# MotorX.net
KiCad netlist of a schematic drawn in Altium Designer
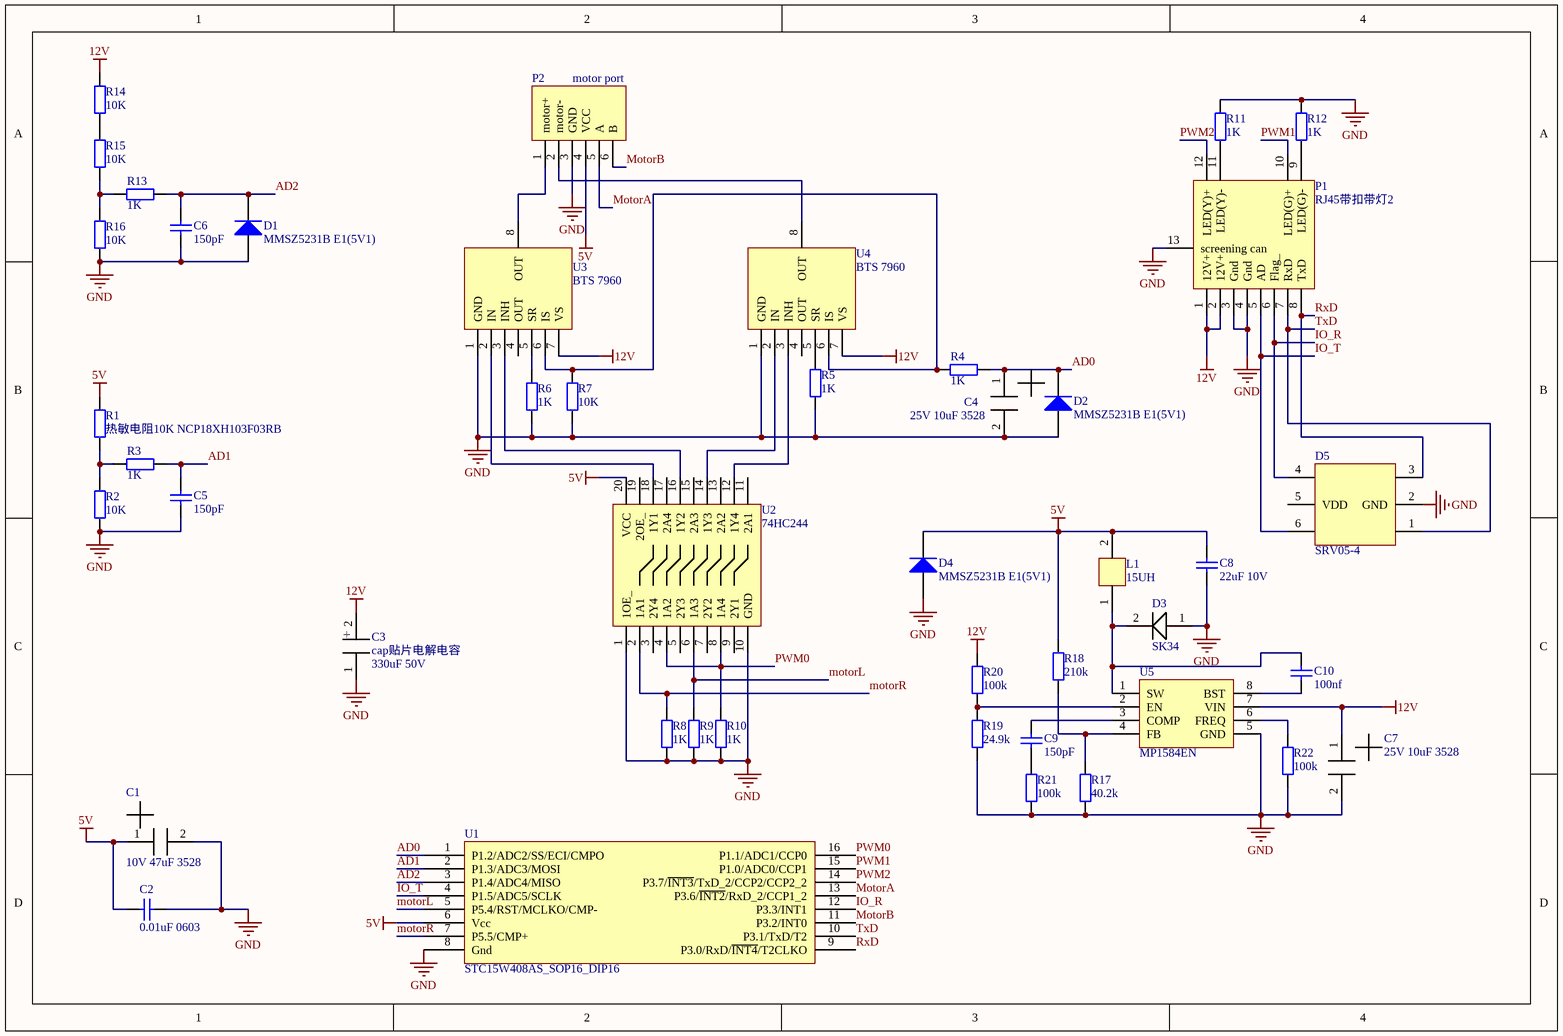
[diagram p0: MotorX.SchDoc]

(export (version "E")
  (design (tool "Eeschema 10.0.6"))
  (components
    (comp (ref "C1")
      (value "10V 47uF 3528")
      (footprint "贴片电容3528_2")
      (libsource (lib "贴片电容3528") (part "电容"))
    )
    (comp (ref "C2")
      (value "0.01uF 0603")
      (footprint "0603")
      (description "Capacitor")
      (fields (field (name "PUBLISHER") "Altium Limited"))
      (libsource (lib "Miscellaneous Devices") (part "Cap"))
    )
    (comp (ref "C3")
      (value "cap贴片电解电容")
      (footprint "贴片电解电容（10*10.2mm）")
      (fields (field (name "ALTIUM_UNNAMED_1") "330uF 50V"))
      (libsource (lib "贴片电容（10x10.2mm）") (part "cap贴片电容"))
    )
    (comp (ref "C4")
      (value "25V 10uF 3528")
      (footprint "贴片电容3528_2")
      (libsource (lib "贴片电容3528") (part "电容"))
    )
    (comp (ref "C5")
      (value "150pF")
      (footprint "0603")
      (description "Capacitor")
      (fields (field (name "Comment") "Cap") (field (name "PUBLISHER") "Altium Limited"))
      (libsource (lib "Miscellaneous Devices") (part "Cap"))
    )
    (comp (ref "C6")
      (value "150pF")
      (footprint "0603")
      (description "Capacitor")
      (fields (field (name "Comment") "Cap") (field (name "PUBLISHER") "Altium Limited"))
      (libsource (lib "Miscellaneous Devices") (part "Cap"))
    )
    (comp (ref "C7")
      (value "25V 10uF 3528")
      (footprint "贴片电容3528_2")
      (libsource (lib "贴片电容3528") (part "电容"))
    )
    (comp (ref "C8")
      (value "22uF 10V")
      (footprint "0805")
      (description "Capacitor")
      (fields (field (name "Comment") "Cap") (field (name "PUBLISHER") "Altium Limited"))
      (libsource (lib "Miscellaneous Devices") (part "Cap"))
    )
    (comp (ref "C9")
      (value "150pF")
      (footprint "0603")
      (description "Capacitor")
      (fields (field (name "Comment") "Cap") (field (name "PUBLISHER") "Altium Limited"))
      (libsource (lib "Miscellaneous Devices") (part "Cap"))
    )
    (comp (ref "C10")
      (value "100nf")
      (footprint "0603")
      (description "Capacitor")
      (fields (field (name "Comment") "Cap") (field (name "PUBLISHER") "Altium Limited"))
      (libsource (lib "Miscellaneous Devices") (part "Cap"))
    )
    (comp (ref "D1")
      (value "MMSZ5231B E1(5V1)")
      (footprint "SOD-123_5")
      (description "High Conductance Fast Diode")
      (fields (field (name "PUBLISHER") "Altium Limited"))
      (libsource (lib "Miscellaneous Devices") (part "Diode 1N4148"))
    )
    (comp (ref "D2")
      (value "MMSZ5231B E1(5V1)")
      (footprint "SOD-123_5")
      (description "High Conductance Fast Diode")
      (fields (field (name "PUBLISHER") "Altium Limited"))
      (libsource (lib "Miscellaneous Devices") (part "Diode 1N4148"))
    )
    (comp (ref "D3") (value "SK34") (footprint "SK34") (libsource (lib "SK34二极管") (part "SK34")))
    (comp (ref "D4")
      (value "MMSZ5231B E1(5V1)")
      (footprint "SOD-123_5")
      (description "High Conductance Fast Diode")
      (fields (field (name "PUBLISHER") "Altium Limited"))
      (libsource (lib "Miscellaneous Devices") (part "Diode 1N4148"))
    )
    (comp (ref "D5")
      (value "SRV05-4")
      (footprint "sot-23-6(SRV05-4)")
      (libsource (lib "SRV05-4") (part "SRV05-4"))
    )
    (comp (ref "L1") (value "15UH") (footprint "0630功率电感") (libsource (lib "0630功率电感") (part "0630功率电感")))
    (comp (ref "P1")
      (value "RJ45带扣带灯2")
      (footprint "RJ45带扣带灯_2")
      (libsource (lib "RJ45带扣带灯2") (part "RJ45带扣带灯2"))
    )
    (comp (ref "P2")
      (value "motor port")
      (footprint "2.54排针")
      (libsource (lib "37-545电机接口") (part "motor port"))
    )
    (comp (ref "R1")
      (value "热敏电阻10K NCP18XH103F03RB")
      (footprint "0603")
      (description "Resistor")
      (fields (field (name "Comment") "Res") (field (name "PUBLISHER") "Altium Limited"))
      (libsource (lib "") (part "Res2_1"))
    )
    (comp (ref "R2")
      (value "10K")
      (footprint "0603")
      (description "Resistor")
      (fields (field (name "Comment") "Res") (field (name "PUBLISHER") "Altium Limited"))
      (libsource (lib "") (part "Res2_1"))
    )
    (comp (ref "R3")
      (value "1K")
      (footprint "0603")
      (description "Resistor")
      (fields (field (name "Comment") "Res") (field (name "PUBLISHER") "Altium Limited"))
      (libsource (lib "Miscellaneous Devices") (part "Res2"))
    )
    (comp (ref "R4")
      (value "1K")
      (footprint "0603")
      (description "Resistor")
      (fields (field (name "Comment") "Res") (field (name "PUBLISHER") "Altium Limited"))
      (libsource (lib "Miscellaneous Devices") (part "Res2"))
    )
    (comp (ref "R5")
      (value "1K")
      (footprint "0603")
      (description "Resistor")
      (fields (field (name "Comment") "Res") (field (name "PUBLISHER") "Altium Limited"))
      (libsource (lib "") (part "Res2_1"))
    )
    (comp (ref "R6")
      (value "1K")
      (footprint "0603")
      (description "Resistor")
      (fields (field (name "Comment") "Res") (field (name "PUBLISHER") "Altium Limited"))
      (libsource (lib "") (part "Res2_1"))
    )
    (comp (ref "R7")
      (value "10K")
      (footprint "0603")
      (description "Resistor")
      (fields (field (name "Comment") "Res") (field (name "PUBLISHER") "Altium Limited"))
      (libsource (lib "") (part "Res2_1"))
    )
    (comp (ref "R8")
      (value "1K")
      (footprint "0603")
      (description "Resistor")
      (fields (field (name "Comment") "Res") (field (name "PUBLISHER") "Altium Limited"))
      (libsource (lib "") (part "Res2_1"))
    )
    (comp (ref "R9")
      (value "1K")
      (footprint "0603")
      (description "Resistor")
      (fields (field (name "Comment") "Res") (field (name "PUBLISHER") "Altium Limited"))
      (libsource (lib "") (part "Res2_1"))
    )
    (comp (ref "R10")
      (value "1K")
      (footprint "0603")
      (description "Resistor")
      (fields (field (name "Comment") "Res") (field (name "PUBLISHER") "Altium Limited"))
      (libsource (lib "") (part "Res2_1"))
    )
    (comp (ref "R11")
      (value "1K")
      (footprint "0603")
      (description "Resistor")
      (fields (field (name "Comment") "Res") (field (name "PUBLISHER") "Altium Limited"))
      (libsource (lib "") (part "Res2_1"))
    )
    (comp (ref "R12")
      (value "1K")
      (footprint "0603")
      (description "Resistor")
      (fields (field (name "Comment") "Res") (field (name "PUBLISHER") "Altium Limited"))
      (libsource (lib "") (part "Res2_1"))
    )
    (comp (ref "R13")
      (value "1K")
      (footprint "0603")
      (description "Resistor")
      (fields (field (name "Comment") "Res") (field (name "PUBLISHER") "Altium Limited"))
      (libsource (lib "Miscellaneous Devices") (part "Res2"))
    )
    (comp (ref "R14")
      (value "10K")
      (footprint "0603")
      (description "Resistor")
      (fields (field (name "Comment") "Res") (field (name "PUBLISHER") "Altium Limited"))
      (libsource (lib "") (part "Res2_1"))
    )
    (comp (ref "R15")
      (value "10K")
      (footprint "0603")
      (description "Resistor")
      (fields (field (name "Comment") "Res") (field (name "PUBLISHER") "Altium Limited"))
      (libsource (lib "") (part "Res2_1"))
    )
    (comp (ref "R16")
      (value "10K")
      (footprint "0603")
      (description "Resistor")
      (fields (field (name "Comment") "Res") (field (name "PUBLISHER") "Altium Limited"))
      (libsource (lib "") (part "Res2_1"))
    )
    (comp (ref "R17")
      (value "40.2k")
      (footprint "0603")
      (description "Resistor")
      (fields (field (name "Comment") "Res") (field (name "PUBLISHER") "Altium Limited"))
      (libsource (lib "") (part "Res2_1"))
    )
    (comp (ref "R18")
      (value "210k")
      (footprint "0603")
      (description "Resistor")
      (fields (field (name "Comment") "Res") (field (name "PUBLISHER") "Altium Limited"))
      (libsource (lib "") (part "Res2_1"))
    )
    (comp (ref "R19")
      (value "24.9k")
      (footprint "0603")
      (description "Resistor")
      (fields (field (name "Comment") "Res") (field (name "PUBLISHER") "Altium Limited"))
      (libsource (lib "") (part "Res2_1"))
    )
    (comp (ref "R20")
      (value "100k")
      (footprint "0603")
      (description "Resistor")
      (fields (field (name "Comment") "Res") (field (name "PUBLISHER") "Altium Limited"))
      (libsource (lib "") (part "Res2_1"))
    )
    (comp (ref "R21")
      (value "100k")
      (footprint "0603")
      (description "Resistor")
      (fields (field (name "Comment") "Res") (field (name "PUBLISHER") "Altium Limited"))
      (libsource (lib "") (part "Res2_1"))
    )
    (comp (ref "R22")
      (value "100k")
      (footprint "0603")
      (description "Resistor")
      (fields (field (name "Comment") "Res") (field (name "PUBLISHER") "Altium Limited"))
      (libsource (lib "") (part "Res2_1"))
    )
    (comp (ref "U1")
      (value "STC15W408AS_SOP16_DIP16")
      (footprint "SOP16")
      (libsource (lib "stcmcu_altium_lib") (part "STC15W401AS_SOP16_DIP16"))
    )
    (comp (ref "U2") (value "74HC244") (footprint "TSSOP-20") (libsource (lib "74HC244") (part "74HC244")))
    (comp (ref "U3") (value "BTS 7960") (footprint "TO-263-7") (libsource (lib "BTS7960") (part "BTS 7960")))
    (comp (ref "U4") (value "BTS 7960") (footprint "TO-263-7") (libsource (lib "BTS7960") (part "BTS 7960")))
    (comp (ref "U5")
      (value "MP1584EN")
      (footprint "MP1584EN")
      (libsource (lib "MP1584EN") (part "Component_1"))
    )
  )
  (nets
    (net (code "1") (name "/AD0") (class "Default")
      (node (ref "C4") (pin "1") (pinfunction "1_1") (pintype "passive"))
      (node (ref "D2") (pin "2") (pinfunction "K_2") (pintype "passive"))
      (node (ref "R4") (pin "2") (pinfunction "2_2") (pintype "passive"))
      (node (ref "U1") (pin "1") (pinfunction "P1.2/ADC2/SS/ECI/CMPO_1") (pintype "passive"))
    )
    (net (code "2") (name "/AD1") (class "Default")
      (node (ref "C5") (pin "2") (pinfunction "2_2") (pintype "passive"))
      (node (ref "R3") (pin "2") (pinfunction "2_2") (pintype "passive"))
      (node (ref "U1") (pin "2") (pinfunction "P1.3/ADC3/MOSI_2") (pintype "passive"))
    )
    (net (code "3") (name "/AD2") (class "Default")
      (node (ref "C6") (pin "2") (pinfunction "2_2") (pintype "passive"))
      (node (ref "D1") (pin "2") (pinfunction "K_2") (pintype "passive"))
      (node (ref "R13") (pin "2") (pinfunction "2_2") (pintype "passive"))
      (node (ref "U1") (pin "3") (pinfunction "P1.4/ADC4/MISO_3") (pintype "passive"))
    )
    (net (code "4") (name "/IO_R") (class "Default")
      (node (ref "D5") (pin "4") (pinfunction "4_4") (pintype "passive"))
      (node (ref "P1") (pin "6") (pinfunction "Flag__6") (pintype "passive"))
      (node (ref "U1") (pin "12") (pinfunction "P3.3/INT1_12") (pintype "passive"))
    )
    (net (code "5") (name "/IO_T") (class "Default")
      (node (ref "D5") (pin "6") (pinfunction "6_6") (pintype "passive"))
      (node (ref "P1") (pin "5") (pinfunction "AD_5") (pintype "passive"))
      (node (ref "U1") (pin "4") (pinfunction "P1.5/ADC5/SCLK_4") (pintype "passive"))
    )
    (net (code "6") (name "/MotorA") (class "Default")
      (node (ref "P2") (pin "5") (pinfunction "A_5") (pintype "passive"))
      (node (ref "U1") (pin "13") (pinfunction "P3.6/~{INT2}/RxD_2/CCP1_2_13") (pintype "passive"))
    )
    (net (code "7") (name "/MotorB") (class "Default")
      (node (ref "P2") (pin "6") (pinfunction "B_6") (pintype "passive"))
      (node (ref "U1") (pin "11") (pinfunction "P3.2/INT0_11") (pintype "passive"))
    )
    (net (code "8") (name "/PWM0") (class "Default")
      (node (ref "R10") (pin "2") (pinfunction "2_2") (pintype "passive"))
      (node (ref "U1") (pin "16") (pinfunction "P1.1/ADC1/CCP0_16") (pintype "passive"))
      (node (ref "U2") (pin "4") (pinfunction "1A2_4") (pintype "passive"))
      (node (ref "U2") (pin "8") (pinfunction "1A4_8") (pintype "passive"))
    )
    (net (code "9") (name "/PWM1") (class "Default")
      (node (ref "P1") (pin "10") (pinfunction "LED(G)+_10") (pintype "passive"))
      (node (ref "U1") (pin "15") (pinfunction "P1.0/ADC0/CCP1_15") (pintype "passive"))
    )
    (net (code "10") (name "/PWM2") (class "Default")
      (node (ref "P1") (pin "12") (pinfunction "LED(Y)+_12") (pintype "passive"))
      (node (ref "U1") (pin "14") (pinfunction "P3.7/~{INT3}/TxD_2/CCP2/CCP2_2_14") (pintype "passive"))
    )
    (net (code "11") (name "/RxD") (class "Default")
      (node (ref "D5") (pin "3") (pinfunction "3_3") (pintype "passive"))
      (node (ref "P1") (pin "8") (pinfunction "TxD_8") (pintype "passive"))
      (node (ref "U1") (pin "9") (pinfunction "P3.0/RxD/~{INT4}/T2CLKO_9") (pintype "passive"))
    )
    (net (code "12") (name "/TxD") (class "Default")
      (node (ref "D5") (pin "1") (pinfunction "1_1") (pintype "passive"))
      (node (ref "P1") (pin "7") (pinfunction "RxD_7") (pintype "passive"))
      (node (ref "U1") (pin "10") (pinfunction "P3.1/TxD/T2_10") (pintype "passive"))
    )
    (net (code "13") (name "/motorL") (class "Default")
      (node (ref "R9") (pin "2") (pinfunction "2_2") (pintype "passive"))
      (node (ref "U1") (pin "5") (pinfunction "P5.4/RST/MCLKO/CMP-_5") (pintype "passive"))
      (node (ref "U2") (pin "6") (pinfunction "1A3_6") (pintype "passive"))
    )
    (net (code "14") (name "/motorR") (class "Default")
      (node (ref "R8") (pin "2") (pinfunction "2_2") (pintype "passive"))
      (node (ref "U1") (pin "7") (pinfunction "P5.5/CMP+_7") (pintype "passive"))
      (node (ref "U2") (pin "2") (pinfunction "1A1_2") (pintype "passive"))
    )
    (net (code "15") (name "5V") (class "Default")
      (node (ref "C1") (pin "1") (pinfunction "1_1") (pintype "passive"))
      (node (ref "C2") (pin "1") (pinfunction "1_1") (pintype "passive"))
      (node (ref "C8") (pin "2") (pinfunction "2_2") (pintype "passive"))
      (node (ref "D4") (pin "2") (pinfunction "K_2") (pintype "passive"))
      (node (ref "L1") (pin "2") (pinfunction "2_2") (pintype "passive"))
      (node (ref "P2") (pin "4") (pinfunction "VCC_4") (pintype "passive"))
      (node (ref "R1") (pin "2") (pinfunction "2_2") (pintype "passive"))
      (node (ref "R18") (pin "2") (pinfunction "2_2") (pintype "passive"))
      (node (ref "U1") (pin "6") (pinfunction "Vcc_6") (pintype "passive"))
      (node (ref "U2") (pin "20") (pinfunction "VCC_20") (pintype "passive"))
    )
    (net (code "16") (name "12V") (class "Default")
      (node (ref "C3") (pin "2") (pinfunction "2_2") (pintype "passive"))
      (node (ref "C7") (pin "1") (pinfunction "1_1") (pintype "passive"))
      (node (ref "P1") (pin "1") (pinfunction "12V+_1") (pintype "passive"))
      (node (ref "P1") (pin "2") (pinfunction "12V+_2") (pintype "passive"))
      (node (ref "R14") (pin "2") (pinfunction "2_2") (pintype "passive"))
      (node (ref "R20") (pin "2") (pinfunction "2_2") (pintype "passive"))
      (node (ref "U3") (pin "7") (pinfunction "VS_7") (pintype "passive"))
      (node (ref "U4") (pin "7") (pinfunction "VS_7") (pintype "passive"))
      (node (ref "U5") (pin "7") (pinfunction "VIN_7") (pintype "passive"))
    )
    (net (code "17") (name "GND") (class "Default")
      (node (ref "C1") (pin "2") (pinfunction "2_2") (pintype "passive"))
      (node (ref "C2") (pin "2") (pinfunction "2_2") (pintype "passive"))
      (node (ref "C3") (pin "1") (pinfunction "1_1") (pintype "passive"))
      (node (ref "C4") (pin "2") (pinfunction "2_2") (pintype "passive"))
      (node (ref "C5") (pin "1") (pinfunction "1_1") (pintype "passive"))
      (node (ref "C6") (pin "1") (pinfunction "1_1") (pintype "passive"))
      (node (ref "C7") (pin "2") (pinfunction "2_2") (pintype "passive"))
      (node (ref "C8") (pin "1") (pinfunction "1_1") (pintype "passive"))
      (node (ref "D1") (pin "1") (pinfunction "A_1") (pintype "passive"))
      (node (ref "D2") (pin "1") (pinfunction "A_1") (pintype "passive"))
      (node (ref "D3") (pin "1") (pinfunction "1_1") (pintype "passive"))
      (node (ref "D4") (pin "1") (pinfunction "A_1") (pintype "passive"))
      (node (ref "D5") (pin "2") (pinfunction "GND_2") (pintype "passive"))
      (node (ref "P1") (pin "13") (pinfunction "screening_can_13") (pintype "passive"))
      (node (ref "P1") (pin "3") (pinfunction "Gnd_3") (pintype "passive"))
      (node (ref "P1") (pin "4") (pinfunction "Gnd_4") (pintype "passive"))
      (node (ref "P2") (pin "3") (pinfunction "GND_3") (pintype "passive"))
      (node (ref "R10") (pin "1") (pinfunction "1_1") (pintype "passive"))
      (node (ref "R11") (pin "2") (pinfunction "2_2") (pintype "passive"))
      (node (ref "R12") (pin "2") (pinfunction "2_2") (pintype "passive"))
      (node (ref "R16") (pin "1") (pinfunction "1_1") (pintype "passive"))
      (node (ref "R17") (pin "1") (pinfunction "1_1") (pintype "passive"))
      (node (ref "R19") (pin "1") (pinfunction "1_1") (pintype "passive"))
      (node (ref "R2") (pin "1") (pinfunction "1_1") (pintype "passive"))
      (node (ref "R21") (pin "1") (pinfunction "1_1") (pintype "passive"))
      (node (ref "R22") (pin "1") (pinfunction "1_1") (pintype "passive"))
      (node (ref "R5") (pin "1") (pinfunction "1_1") (pintype "passive"))
      (node (ref "R6") (pin "1") (pinfunction "1_1") (pintype "passive"))
      (node (ref "R7") (pin "1") (pinfunction "1_1") (pintype "passive"))
      (node (ref "R8") (pin "1") (pinfunction "1_1") (pintype "passive"))
      (node (ref "R9") (pin "1") (pinfunction "1_1") (pintype "passive"))
      (node (ref "U1") (pin "8") (pinfunction "Gnd_8") (pintype "passive"))
      (node (ref "U2") (pin "1") (pinfunction "1OE__1") (pintype "passive"))
      (node (ref "U2") (pin "10") (pinfunction "GND_10") (pintype "passive"))
      (node (ref "U3") (pin "1") (pinfunction "GND_1") (pintype "passive"))
      (node (ref "U4") (pin "1") (pinfunction "GND_1") (pintype "passive"))
      (node (ref "U5") (pin "5") (pinfunction "GND_5") (pintype "passive"))
    )
    (net (code "18") (name "Net-(C9-Pad1)") (class "Default")
      (node (ref "C9") (pin "1") (pinfunction "1_1") (pintype "passive"))
      (node (ref "R21") (pin "2") (pinfunction "2_2") (pintype "passive"))
    )
    (net (code "19") (name "Net-(P1-LED(G)-)") (class "Default")
      (node (ref "P1") (pin "9") (pinfunction "LED(G)-_9") (pintype "passive"))
      (node (ref "R12") (pin "1") (pinfunction "1_1") (pintype "passive"))
    )
    (net (code "20") (name "Net-(P1-LED(Y)-)") (class "Default")
      (node (ref "P1") (pin "11") (pinfunction "LED(Y)-_11") (pintype "passive"))
      (node (ref "R11") (pin "1") (pinfunction "1_1") (pintype "passive"))
    )
    (net (code "21") (name "Net-(P2-motor+)") (class "Default")
      (node (ref "P2") (pin "1") (pinfunction "motor+_1") (pintype "passive"))
      (node (ref "U3") (pin "8") (pinfunction "OUT_8") (pintype "passive"))
    )
    (net (code "22") (name "Net-(P2-motor-)") (class "Default")
      (node (ref "P2") (pin "2") (pinfunction "motor-_2") (pintype "passive"))
      (node (ref "U4") (pin "8") (pinfunction "OUT_8") (pintype "passive"))
    )
    (net (code "23") (name "Net-(R1-Pad1)") (class "Default")
      (node (ref "R1") (pin "1") (pinfunction "1_1") (pintype "passive"))
      (node (ref "R2") (pin "2") (pinfunction "2_2") (pintype "passive"))
      (node (ref "R3") (pin "1") (pinfunction "1_1") (pintype "passive"))
    )
    (net (code "24") (name "Net-(R13-Pad1)") (class "Default")
      (node (ref "R13") (pin "1") (pinfunction "1_1") (pintype "passive"))
      (node (ref "R15") (pin "1") (pinfunction "1_1") (pintype "passive"))
      (node (ref "R16") (pin "2") (pinfunction "2_2") (pintype "passive"))
    )
    (net (code "25") (name "Net-(R14-Pad1)") (class "Default")
      (node (ref "R14") (pin "1") (pinfunction "1_1") (pintype "passive"))
      (node (ref "R15") (pin "2") (pinfunction "2_2") (pintype "passive"))
    )
    (net (code "26") (name "Net-(U2-1Y1)") (class "Default")
      (node (ref "U2") (pin "18") (pinfunction "1Y1_18") (pintype "passive"))
      (node (ref "U3") (pin "2") (pinfunction "IN_2") (pintype "passive"))
    )
    (net (code "27") (name "Net-(U2-1Y2)") (class "Default")
      (node (ref "U2") (pin "16") (pinfunction "1Y2_16") (pintype "passive"))
      (node (ref "U3") (pin "3") (pinfunction "INH_3") (pintype "passive"))
    )
    (net (code "28") (name "Net-(U2-1Y3)") (class "Default")
      (node (ref "U2") (pin "14") (pinfunction "1Y3_14") (pintype "passive"))
      (node (ref "U4") (pin "2") (pinfunction "IN_2") (pintype "passive"))
    )
    (net (code "29") (name "Net-(U2-1Y4)") (class "Default")
      (node (ref "U2") (pin "12") (pinfunction "1Y4_12") (pintype "passive"))
      (node (ref "U4") (pin "3") (pinfunction "INH_3") (pintype "passive"))
    )
    (net (code "30") (name "Net-(U3-IS)") (class "Default")
      (node (ref "R4") (pin "1") (pinfunction "1_1") (pintype "passive"))
      (node (ref "R7") (pin "2") (pinfunction "2_2") (pintype "passive"))
      (node (ref "U3") (pin "6") (pinfunction "IS_6") (pintype "passive"))
      (node (ref "U4") (pin "6") (pinfunction "IS_6") (pintype "passive"))
    )
    (net (code "31") (name "Net-(U3-SR)") (class "Default")
      (node (ref "R6") (pin "2") (pinfunction "2_2") (pintype "passive"))
      (node (ref "U3") (pin "5") (pinfunction "SR_5") (pintype "passive"))
    )
    (net (code "32") (name "Net-(U4-SR)") (class "Default")
      (node (ref "R5") (pin "2") (pinfunction "2_2") (pintype "passive"))
      (node (ref "U4") (pin "5") (pinfunction "SR_5") (pintype "passive"))
    )
    (net (code "33") (name "Net-(U5-BST)") (class "Default")
      (node (ref "C10") (pin "1") (pinfunction "1_1") (pintype "passive"))
      (node (ref "U5") (pin "8") (pinfunction "BST_8") (pintype "passive"))
    )
    (net (code "34") (name "Net-(U5-COMP)") (class "Default")
      (node (ref "C9") (pin "2") (pinfunction "2_2") (pintype "passive"))
      (node (ref "U5") (pin "3") (pinfunction "COMP_3") (pintype "passive"))
    )
    (net (code "35") (name "Net-(U5-EN)") (class "Default")
      (node (ref "R19") (pin "2") (pinfunction "2_2") (pintype "passive"))
      (node (ref "R20") (pin "1") (pinfunction "1_1") (pintype "passive"))
      (node (ref "U5") (pin "2") (pinfunction "EN_2") (pintype "passive"))
    )
    (net (code "36") (name "Net-(U5-FB)") (class "Default")
      (node (ref "R17") (pin "2") (pinfunction "2_2") (pintype "passive"))
      (node (ref "R18") (pin "1") (pinfunction "1_1") (pintype "passive"))
      (node (ref "U5") (pin "4") (pinfunction "FB_4") (pintype "passive"))
    )
    (net (code "37") (name "Net-(U5-FREQ)") (class "Default")
      (node (ref "R22") (pin "2") (pinfunction "2_2") (pintype "passive"))
      (node (ref "U5") (pin "6") (pinfunction "FREQ_6") (pintype "passive"))
    )
    (net (code "38") (name "Net-(U5-SW)") (class "Default")
      (node (ref "C10") (pin "2") (pinfunction "2_2") (pintype "passive"))
      (node (ref "D3") (pin "2") (pinfunction "2_2") (pintype "passive"))
      (node (ref "L1") (pin "1") (pinfunction "2_1") (pintype "passive"))
      (node (ref "U5") (pin "1") (pinfunction "SW_1") (pintype "passive"))
    )
    (net (code "39") (name "unconnected-(D5-VDD-Pad5)") (class "Default")
      (node (ref "D5") (pin "5") (pinfunction "VDD_5") (pintype "passive"))
    )
    (net (code "40") (name "unconnected-(U2-2A1-Pad11)") (class "Default")
      (node (ref "U2") (pin "11") (pinfunction "2A1_11") (pintype "passive"))
    )
    (net (code "41") (name "unconnected-(U2-2A2-Pad13)") (class "Default")
      (node (ref "U2") (pin "13") (pinfunction "2A2_13") (pintype "passive"))
    )
    (net (code "42") (name "unconnected-(U2-2A3-Pad15)") (class "Default")
      (node (ref "U2") (pin "15") (pinfunction "2A3_15") (pintype "passive"))
    )
    (net (code "43") (name "unconnected-(U2-2A4-Pad17)") (class "Default")
      (node (ref "U2") (pin "17") (pinfunction "2A4_17") (pintype "passive"))
    )
    (net (code "44") (name "unconnected-(U2-2OE_-Pad19)") (class "Default")
      (node (ref "U2") (pin "19") (pinfunction "2OE__19") (pintype "passive"))
    )
    (net (code "45") (name "unconnected-(U2-2Y1-Pad9)") (class "Default")
      (node (ref "U2") (pin "9") (pinfunction "2Y1_9") (pintype "passive"))
    )
    (net (code "46") (name "unconnected-(U2-2Y2-Pad7)") (class "Default")
      (node (ref "U2") (pin "7") (pinfunction "2Y2_7") (pintype "passive"))
    )
    (net (code "47") (name "unconnected-(U2-2Y3-Pad5)") (class "Default")
      (node (ref "U2") (pin "5") (pinfunction "2Y3_5") (pintype "passive"))
    )
    (net (code "48") (name "unconnected-(U2-2Y4-Pad3)") (class "Default")
      (node (ref "U2") (pin "3") (pinfunction "2Y4_3") (pintype "passive"))
    )
    (net (code "49") (name "unconnected-(U3-OUT-Pad4)") (class "Default")
      (node (ref "U3") (pin "4") (pinfunction "OUT_4") (pintype "passive"))
    )
    (net (code "50") (name "unconnected-(U4-OUT-Pad4)") (class "Default")
      (node (ref "U4") (pin "4") (pinfunction "OUT_4") (pintype "passive"))
    )
  )
)
